# USB.net
KiCad netlist of a schematic drawn in Altium Designer
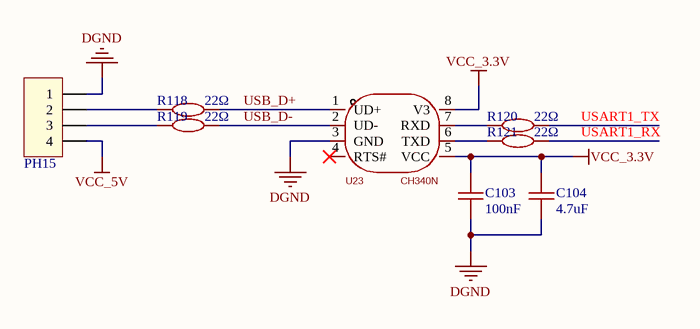
[diagram p0: USB.SchDoc]

(export (version "E")
  (design (tool "Eeschema 10.0.6"))
  (components
    (comp (ref "C103")
      (value "100nF")
      (footprint "C0603")
      (description "贴片电容,X7R")
      (libsource (lib "XG_DW_POCT_2K10LED_3") (part "100nF/50V,C0603"))
    )
    (comp (ref "C104")
      (value "4.7uF")
      (footprint "C0603")
      (description "贴片电容,X7R")
      (libsource (lib "XG_DW_POCT_2K10LED_3") (part "4.7uF/50V,C0603"))
    )
    (comp (ref "PH15")
      (value "PH2.0-4P")
      (footprint "PH2.0-4P 弯针")
      (libsource (lib "XG_DW_POCT_2K10LED_3") (part "PH2.0-4P"))
    )
    (comp (ref "R118")
      (value "22Ω")
      (footprint "R0603")
      (description "电阻类型:厚膜电阻;阻值:22Ω;精度:±1%;功率:100mW;最大工作电压:75V;温度系数:±100ppm/℃;")
      (libsource (lib "XG_DW_POCT_2K10LED_3") (part "22Ω,R0603"))
    )
    (comp (ref "R119")
      (value "22Ω")
      (footprint "R0603")
      (description "电阻类型:厚膜电阻;阻值:22Ω;精度:±1%;功率:100mW;最大工作电压:75V;温度系数:±100ppm/℃;")
      (libsource (lib "XG_DW_POCT_2K10LED_3") (part "22Ω,R0603"))
    )
    (comp (ref "R120")
      (value "22Ω")
      (footprint "R0603")
      (description "电阻类型:厚膜电阻;阻值:22Ω;精度:±1%;功率:100mW;最大工作电压:75V;温度系数:±100ppm/℃;")
      (libsource (lib "XG_DW_POCT_2K10LED_3") (part "22Ω,R0603"))
    )
    (comp (ref "R121")
      (value "22Ω")
      (footprint "R0603")
      (description "电阻类型:厚膜电阻;阻值:22Ω;精度:±1%;功率:100mW;最大工作电压:75V;温度系数:±100ppm/℃;")
      (libsource (lib "XG_DW_POCT_2K10LED_3") (part "22Ω,R0603"))
    )
    (comp (ref "U23")
      (value "CH340N")
      (footprint "SOP-8_L4.9-W3.9-P1.27-LS6.0-BL")
      (fields (field (name "MANUFACTURER") "WCH(南京沁恒)"))
      (libsource (lib "XG_DW_POCT_2K10LED_3") (part "CH340N"))
    )
  )
  (nets
    (net (code "1") (name "/USART1_RX") (class "Default")
      (node (ref "R121") (pin "2") (pinfunction "2_2") (pintype "passive"))
    )
    (net (code "2") (name "/USART1_TX") (class "Default")
      (node (ref "R120") (pin "2") (pinfunction "2_2") (pintype "passive"))
    )
    (net (code "3") (name "/USB_D+") (class "Default")
      (node (ref "R118") (pin "2") (pinfunction "2_2") (pintype "passive"))
      (node (ref "U23") (pin "1") (pinfunction "UD+_1") (pintype "passive"))
    )
    (net (code "4") (name "/USB_D-") (class "Default")
      (node (ref "R119") (pin "2") (pinfunction "2_2") (pintype "passive"))
      (node (ref "U23") (pin "2") (pinfunction "UD-_2") (pintype "passive"))
    )
    (net (code "5") (name "DGND") (class "Default")
      (node (ref "C103") (pin "1") (pinfunction "1_1") (pintype "passive"))
      (node (ref "C104") (pin "1") (pinfunction "1_1") (pintype "passive"))
      (node (ref "PH15") (pin "1") (pinfunction "1_1") (pintype "passive"))
      (node (ref "U23") (pin "3") (pinfunction "GND_3") (pintype "passive"))
    )
    (net (code "6") (name "Net-(PH15-Pad2)") (class "Default")
      (node (ref "PH15") (pin "2") (pinfunction "2_2") (pintype "passive"))
      (node (ref "R118") (pin "1") (pinfunction "1_1") (pintype "passive"))
    )
    (net (code "7") (name "Net-(PH15-Pad3)") (class "Default")
      (node (ref "PH15") (pin "3") (pinfunction "3_3") (pintype "passive"))
      (node (ref "R119") (pin "1") (pinfunction "1_1") (pintype "passive"))
    )
    (net (code "8") (name "Net-(U23-RXD)") (class "Default")
      (node (ref "R120") (pin "1") (pinfunction "1_1") (pintype "passive"))
      (node (ref "U23") (pin "7") (pinfunction "RXD_7") (pintype "passive"))
    )
    (net (code "9") (name "Net-(U23-TXD)") (class "Default")
      (node (ref "R121") (pin "1") (pinfunction "1_1") (pintype "passive"))
      (node (ref "U23") (pin "6") (pinfunction "TXD_6") (pintype "passive"))
    )
    (net (code "10") (name "VCC_3.3V") (class "Default")
      (node (ref "C103") (pin "2") (pinfunction "2_2") (pintype "passive"))
      (node (ref "C104") (pin "2") (pinfunction "2_2") (pintype "passive"))
      (node (ref "U23") (pin "5") (pinfunction "VCC_5") (pintype "passive"))
      (node (ref "U23") (pin "8") (pinfunction "V3_8") (pintype "passive"))
    )
    (net (code "11") (name "VCC_5V") (class "Default")
      (node (ref "PH15") (pin "4") (pinfunction "4_4") (pintype "passive"))
    )
    (net (code "12") (name "unconnected-(U23-RTS#-Pad4)") (class "Default")
      (node (ref "U23") (pin "4") (pinfunction "RTS#_4") (pintype "passive+no_connect"))
    )
  )
)
